# ftExtender2v0.net
KiCad netlist of a schematic drawn in EAGLE
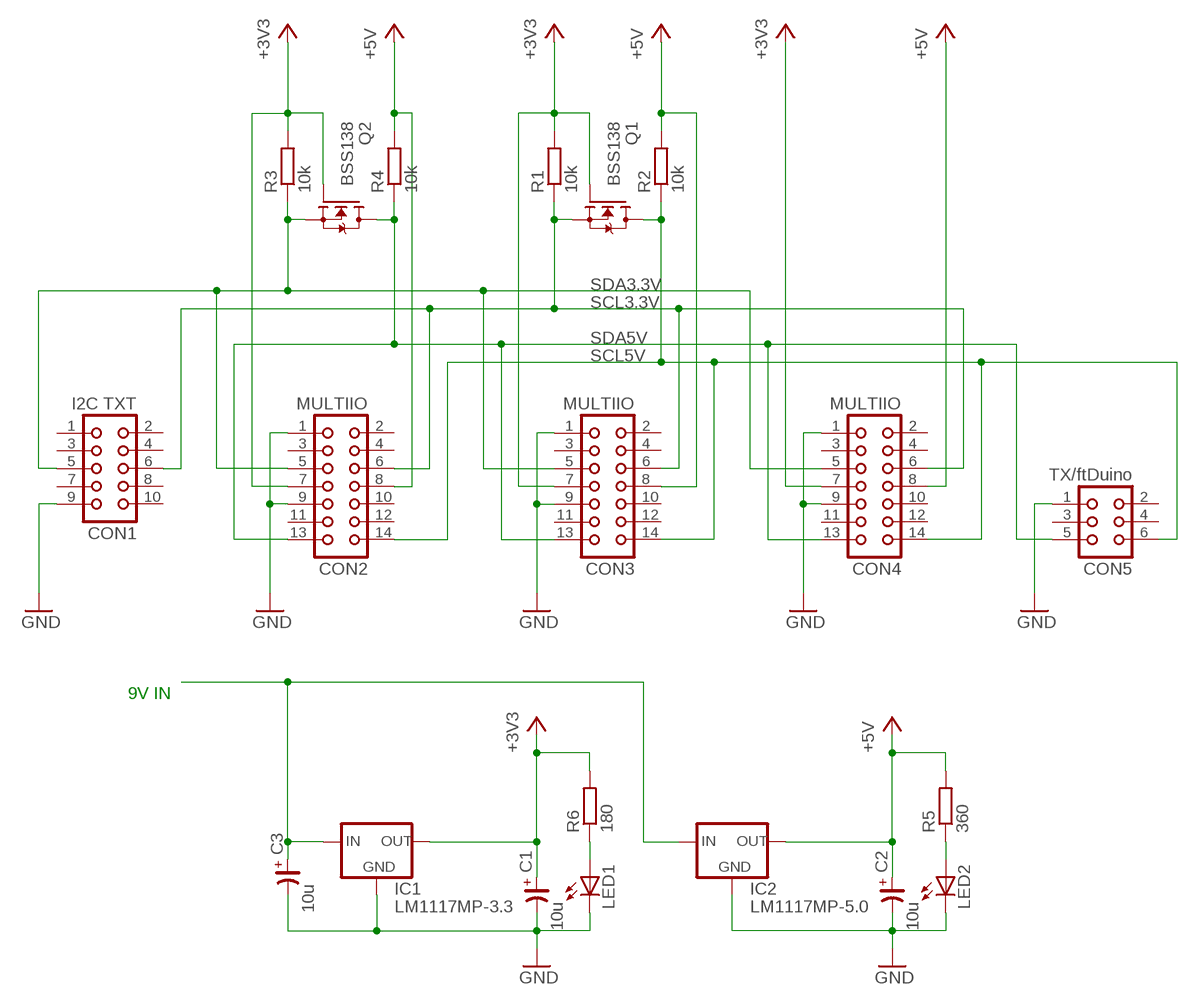
[diagram p0: schematic, sheet 1]

(export (version "E")
  (design (tool "Eeschema 10.0.6"))
  (components
    (comp (ref "C1")
      (value "10u")
      (footprint "eagle-import:C6032_T")
      (libsource (lib "eagle-import") (part "CP_6032"))
    )
    (comp (ref "C2")
      (value "10u")
      (footprint "eagle-import:C6032_T")
      (libsource (lib "eagle-import") (part "CP_6032"))
    )
    (comp (ref "C3")
      (value "10u")
      (footprint "eagle-import:C6032_T")
      (libsource (lib "eagle-import") (part "CP_6032"))
    )
    (comp (ref "CON1")
      (value "I2C TXT")
      (footprint "eagle-import:CON10")
      (libsource (lib "eagle-import") (part "CON10"))
    )
    (comp (ref "CON2")
      (value "MULTIIO")
      (footprint "eagle-import:CON14")
      (libsource (lib "eagle-import") (part "CON14"))
    )
    (comp (ref "CON3")
      (value "MULTIIO")
      (footprint "eagle-import:CON14")
      (libsource (lib "eagle-import") (part "CON14"))
    )
    (comp (ref "CON4")
      (value "MULTIIO")
      (footprint "eagle-import:CON14")
      (libsource (lib "eagle-import") (part "CON14"))
    )
    (comp (ref "CON5")
      (value "TX/ftDuino")
      (footprint "eagle-import:CON06")
      (libsource (lib "eagle-import") (part "CON06"))
    )
    (comp (ref "IC1")
      (value "LM1117MP-3.3")
      (footprint "eagle-import:SOT223")
      (fields (field (name "MF") "Texas Instruments"))
      (libsource (lib "eagle-import") (part "LM1117?-MP3.3"))
    )
    (comp (ref "IC2")
      (value "LM1117MP-5.0")
      (footprint "eagle-import:SOT223")
      (fields (field (name "MF") "Texas Instruments"))
      (libsource (lib "eagle-import") (part "LM1117?-MP5.0"))
    )
    (comp (ref "LED1")
      (value "LEDCHIP-LED0805")
      (footprint "eagle-import:CHIP-LED0805")
      (libsource (lib "eagle-import") (part "LEDCHIP-LED0805"))
    )
    (comp (ref "LED2")
      (value "LEDCHIP-LED0805")
      (footprint "eagle-import:CHIP-LED0805")
      (libsource (lib "eagle-import") (part "LEDCHIP-LED0805"))
    )
    (comp (ref "Q1")
      (value "BSS138")
      (footprint "eagle-import:SOT23")
      (fields (field (name "MF") "Fairchild"))
      (libsource (lib "eagle-import") (part "BSS138"))
    )
    (comp (ref "Q2")
      (value "BSS138")
      (footprint "eagle-import:SOT23")
      (fields (field (name "MF") "Fairchild"))
      (libsource (lib "eagle-import") (part "BSS138"))
    )
    (comp (ref "R1")
      (value "10k")
      (footprint "eagle-import:R1206")
      (libsource (lib "eagle-import") (part "R-EU_R1206"))
    )
    (comp (ref "R2")
      (value "10k")
      (footprint "eagle-import:R1206")
      (libsource (lib "eagle-import") (part "R-EU_R1206"))
    )
    (comp (ref "R3")
      (value "10k")
      (footprint "eagle-import:R1206")
      (libsource (lib "eagle-import") (part "R-EU_R1206"))
    )
    (comp (ref "R4")
      (value "10k")
      (footprint "eagle-import:R1206")
      (libsource (lib "eagle-import") (part "R-EU_R1206"))
    )
    (comp (ref "R5")
      (value "360")
      (footprint "eagle-import:R1206")
      (libsource (lib "eagle-import") (part "R-EU_R1206"))
    )
    (comp (ref "R6")
      (value "180")
      (footprint "eagle-import:R1206")
      (libsource (lib "eagle-import") (part "R-EU_R1206"))
    )
  )
  (nets
    (net (code "1") (name "+3V3") (class "Default")
      (node (ref "C1") (pin "+") (pinfunction "+_+") (pintype "passive"))
      (node (ref "CON2") (pin "7") (pinfunction "7_7") (pintype "passive"))
      (node (ref "CON3") (pin "7") (pinfunction "7_7") (pintype "passive"))
      (node (ref "CON4") (pin "7") (pinfunction "7_7") (pintype "passive"))
      (node (ref "IC1") (pin "2") (pinfunction "OUT_2") (pintype "passive"))
      (node (ref "IC1") (pin "4") (pinfunction "OUT_4") (pintype "passive"))
      (node (ref "Q1") (pin "1") (pinfunction "G_1") (pintype "passive"))
      (node (ref "Q2") (pin "1") (pinfunction "G_1") (pintype "passive"))
      (node (ref "R1") (pin "2") (pinfunction "2_2") (pintype "passive"))
      (node (ref "R3") (pin "2") (pinfunction "2_2") (pintype "passive"))
      (node (ref "R6") (pin "2") (pinfunction "2_2") (pintype "passive"))
    )
    (net (code "2") (name "+5V") (class "Default")
      (node (ref "C2") (pin "+") (pinfunction "+_+") (pintype "passive"))
      (node (ref "CON2") (pin "8") (pinfunction "8_8") (pintype "passive"))
      (node (ref "CON3") (pin "8") (pinfunction "8_8") (pintype "passive"))
      (node (ref "CON4") (pin "8") (pinfunction "8_8") (pintype "passive"))
      (node (ref "IC2") (pin "2") (pinfunction "OUT_2") (pintype "passive"))
      (node (ref "IC2") (pin "4") (pinfunction "OUT_4") (pintype "passive"))
      (node (ref "R2") (pin "2") (pinfunction "2_2") (pintype "passive"))
      (node (ref "R4") (pin "2") (pinfunction "2_2") (pintype "passive"))
      (node (ref "R5") (pin "2") (pinfunction "2_2") (pintype "passive"))
    )
    (net (code "3") (name "/SCL3.3V") (class "Default")
      (node (ref "CON1") (pin "6") (pinfunction "6_6") (pintype "passive"))
      (node (ref "CON2") (pin "6") (pinfunction "6_6") (pintype "passive"))
      (node (ref "CON3") (pin "6") (pinfunction "6_6") (pintype "passive"))
      (node (ref "CON4") (pin "6") (pinfunction "6_6") (pintype "passive"))
      (node (ref "Q1") (pin "2") (pinfunction "S_2") (pintype "passive"))
      (node (ref "R1") (pin "1") (pinfunction "1_1") (pintype "passive"))
    )
    (net (code "4") (name "/SCL5V") (class "Default")
      (node (ref "CON2") (pin "14") (pinfunction "14_14") (pintype "passive"))
      (node (ref "CON3") (pin "14") (pinfunction "14_14") (pintype "passive"))
      (node (ref "CON4") (pin "14") (pinfunction "14_14") (pintype "passive"))
      (node (ref "CON5") (pin "6") (pinfunction "6_6") (pintype "passive"))
      (node (ref "Q1") (pin "3") (pinfunction "D_3") (pintype "passive"))
      (node (ref "R2") (pin "1") (pinfunction "1_1") (pintype "passive"))
    )
    (net (code "5") (name "/SDA3.3V") (class "Default")
      (node (ref "CON1") (pin "5") (pinfunction "5_5") (pintype "passive"))
      (node (ref "CON2") (pin "5") (pinfunction "5_5") (pintype "passive"))
      (node (ref "CON3") (pin "5") (pinfunction "5_5") (pintype "passive"))
      (node (ref "CON4") (pin "5") (pinfunction "5_5") (pintype "passive"))
      (node (ref "Q2") (pin "2") (pinfunction "S_2") (pintype "passive"))
      (node (ref "R3") (pin "1") (pinfunction "1_1") (pintype "passive"))
    )
    (net (code "6") (name "/SDA5V") (class "Default")
      (node (ref "CON2") (pin "13") (pinfunction "13_13") (pintype "passive"))
      (node (ref "CON3") (pin "13") (pinfunction "13_13") (pintype "passive"))
      (node (ref "CON4") (pin "13") (pinfunction "13_13") (pintype "passive"))
      (node (ref "CON5") (pin "5") (pinfunction "5_5") (pintype "passive"))
      (node (ref "Q2") (pin "3") (pinfunction "D_3") (pintype "passive"))
      (node (ref "R4") (pin "1") (pinfunction "1_1") (pintype "passive"))
    )
    (net (code "7") (name "GND") (class "Default")
      (node (ref "C1") (pin "-") (pinfunction "-_-") (pintype "passive"))
      (node (ref "C2") (pin "-") (pinfunction "-_-") (pintype "passive"))
      (node (ref "C3") (pin "-") (pinfunction "-_-") (pintype "passive"))
      (node (ref "CON1") (pin "9") (pinfunction "9_9") (pintype "passive"))
      (node (ref "CON2") (pin "1") (pinfunction "1_1") (pintype "passive"))
      (node (ref "CON2") (pin "9") (pinfunction "9_9") (pintype "passive"))
      (node (ref "CON3") (pin "1") (pinfunction "1_1") (pintype "passive"))
      (node (ref "CON3") (pin "9") (pinfunction "9_9") (pintype "passive"))
      (node (ref "CON4") (pin "1") (pinfunction "1_1") (pintype "passive"))
      (node (ref "CON4") (pin "9") (pinfunction "9_9") (pintype "passive"))
      (node (ref "CON5") (pin "1") (pinfunction "1_1") (pintype "passive"))
      (node (ref "IC1") (pin "1") (pinfunction "GND_1") (pintype "input"))
      (node (ref "IC2") (pin "1") (pinfunction "GND_1") (pintype "input"))
      (node (ref "LED1") (pin "C") (pinfunction "C_C") (pintype "passive"))
      (node (ref "LED2") (pin "C") (pinfunction "C_C") (pintype "passive"))
    )
    (net (code "8") (name "Net-(IC1-IN)") (class "Default")
      (node (ref "C3") (pin "+") (pinfunction "+_+") (pintype "passive"))
      (node (ref "IC1") (pin "3") (pinfunction "IN_3") (pintype "input"))
      (node (ref "IC2") (pin "3") (pinfunction "IN_3") (pintype "input"))
    )
    (net (code "9") (name "Net-(LED1-PadA)") (class "Default")
      (node (ref "LED1") (pin "A") (pinfunction "A_A") (pintype "passive"))
      (node (ref "R6") (pin "1") (pinfunction "1_1") (pintype "passive"))
    )
    (net (code "10") (name "Net-(LED2-PadA)") (class "Default")
      (node (ref "LED2") (pin "A") (pinfunction "A_A") (pintype "passive"))
      (node (ref "R5") (pin "1") (pinfunction "1_1") (pintype "passive"))
    )
    (net (code "11") (name "unconnected-(CON1-Pad1)") (class "Default")
      (node (ref "CON1") (pin "1") (pinfunction "1_1") (pintype "passive"))
    )
    (net (code "12") (name "unconnected-(CON1-Pad2)") (class "Default")
      (node (ref "CON1") (pin "2") (pinfunction "2_2") (pintype "passive"))
    )
    (net (code "13") (name "unconnected-(CON1-Pad3)") (class "Default")
      (node (ref "CON1") (pin "3") (pinfunction "3_3") (pintype "passive"))
    )
    (net (code "14") (name "unconnected-(CON1-Pad4)") (class "Default")
      (node (ref "CON1") (pin "4") (pinfunction "4_4") (pintype "passive"))
    )
    (net (code "15") (name "unconnected-(CON1-Pad7)") (class "Default")
      (node (ref "CON1") (pin "7") (pinfunction "7_7") (pintype "passive"))
    )
    (net (code "16") (name "unconnected-(CON1-Pad8)") (class "Default")
      (node (ref "CON1") (pin "8") (pinfunction "8_8") (pintype "passive"))
    )
    (net (code "17") (name "unconnected-(CON1-Pad10)") (class "Default")
      (node (ref "CON1") (pin "10") (pinfunction "10_10") (pintype "passive"))
    )
    (net (code "18") (name "unconnected-(CON2-Pad2)") (class "Default")
      (node (ref "CON2") (pin "2") (pinfunction "2_2") (pintype "passive"))
    )
    (net (code "19") (name "unconnected-(CON2-Pad3)") (class "Default")
      (node (ref "CON2") (pin "3") (pinfunction "3_3") (pintype "passive"))
    )
    (net (code "20") (name "unconnected-(CON2-Pad4)") (class "Default")
      (node (ref "CON2") (pin "4") (pinfunction "4_4") (pintype "passive"))
    )
    (net (code "21") (name "unconnected-(CON2-Pad10)") (class "Default")
      (node (ref "CON2") (pin "10") (pinfunction "10_10") (pintype "passive"))
    )
    (net (code "22") (name "unconnected-(CON2-Pad11)") (class "Default")
      (node (ref "CON2") (pin "11") (pinfunction "11_11") (pintype "passive"))
    )
    (net (code "23") (name "unconnected-(CON2-Pad12)") (class "Default")
      (node (ref "CON2") (pin "12") (pinfunction "12_12") (pintype "passive"))
    )
    (net (code "24") (name "unconnected-(CON3-Pad2)") (class "Default")
      (node (ref "CON3") (pin "2") (pinfunction "2_2") (pintype "passive"))
    )
    (net (code "25") (name "unconnected-(CON3-Pad3)") (class "Default")
      (node (ref "CON3") (pin "3") (pinfunction "3_3") (pintype "passive"))
    )
    (net (code "26") (name "unconnected-(CON3-Pad4)") (class "Default")
      (node (ref "CON3") (pin "4") (pinfunction "4_4") (pintype "passive"))
    )
    (net (code "27") (name "unconnected-(CON3-Pad10)") (class "Default")
      (node (ref "CON3") (pin "10") (pinfunction "10_10") (pintype "passive"))
    )
    (net (code "28") (name "unconnected-(CON3-Pad11)") (class "Default")
      (node (ref "CON3") (pin "11") (pinfunction "11_11") (pintype "passive"))
    )
    (net (code "29") (name "unconnected-(CON3-Pad12)") (class "Default")
      (node (ref "CON3") (pin "12") (pinfunction "12_12") (pintype "passive"))
    )
    (net (code "30") (name "unconnected-(CON4-Pad2)") (class "Default")
      (node (ref "CON4") (pin "2") (pinfunction "2_2") (pintype "passive"))
    )
    (net (code "31") (name "unconnected-(CON4-Pad3)") (class "Default")
      (node (ref "CON4") (pin "3") (pinfunction "3_3") (pintype "passive"))
    )
    (net (code "32") (name "unconnected-(CON4-Pad4)") (class "Default")
      (node (ref "CON4") (pin "4") (pinfunction "4_4") (pintype "passive"))
    )
    (net (code "33") (name "unconnected-(CON4-Pad10)") (class "Default")
      (node (ref "CON4") (pin "10") (pinfunction "10_10") (pintype "passive"))
    )
    (net (code "34") (name "unconnected-(CON4-Pad11)") (class "Default")
      (node (ref "CON4") (pin "11") (pinfunction "11_11") (pintype "passive"))
    )
    (net (code "35") (name "unconnected-(CON4-Pad12)") (class "Default")
      (node (ref "CON4") (pin "12") (pinfunction "12_12") (pintype "passive"))
    )
    (net (code "36") (name "unconnected-(CON5-Pad2)") (class "Default")
      (node (ref "CON5") (pin "2") (pinfunction "2_2") (pintype "passive"))
    )
    (net (code "37") (name "unconnected-(CON5-Pad3)") (class "Default")
      (node (ref "CON5") (pin "3") (pinfunction "3_3") (pintype "passive"))
    )
    (net (code "38") (name "unconnected-(CON5-Pad4)") (class "Default")
      (node (ref "CON5") (pin "4") (pinfunction "4_4") (pintype "passive"))
    )
  )
)
